# eLite_Clock_-_Display_Boards.net
KiCad netlist of a schematic drawn in EAGLE
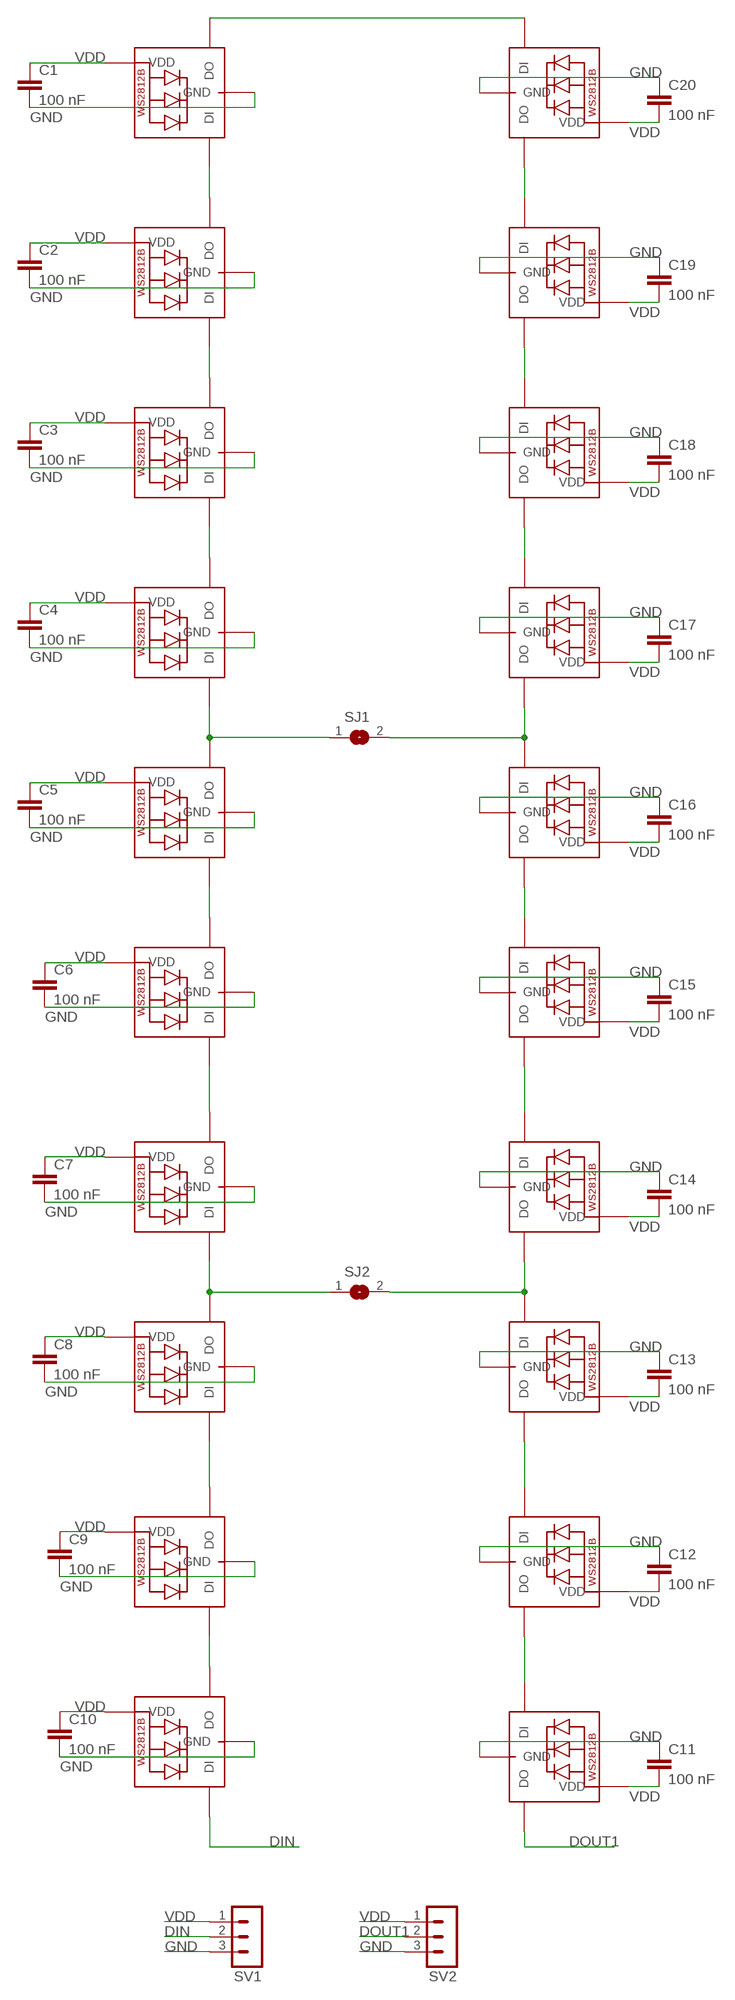
[diagram p0: schematic, sheet 1]

(export (version "E")
  (design (tool "Eeschema 10.0.6"))
  (components
    (comp (ref "C1")
      (value "100 nF")
      (footprint "eagle-import:C025-025X050")
      (libsource (lib "eagle-import") (part "C-EU025-025X050"))
    )
    (comp (ref "C2")
      (value "100 nF")
      (footprint "eagle-import:C025-025X050")
      (libsource (lib "eagle-import") (part "C-EU025-025X050"))
    )
    (comp (ref "C3")
      (value "100 nF")
      (footprint "eagle-import:C025-025X050")
      (libsource (lib "eagle-import") (part "C-EU025-025X050"))
    )
    (comp (ref "C4")
      (value "100 nF")
      (footprint "eagle-import:C025-025X050")
      (libsource (lib "eagle-import") (part "C-EU025-025X050"))
    )
    (comp (ref "C5")
      (value "100 nF")
      (footprint "eagle-import:C025-025X050")
      (libsource (lib "eagle-import") (part "C-EU025-025X050"))
    )
    (comp (ref "C6")
      (value "100 nF")
      (footprint "eagle-import:C025-025X050")
      (libsource (lib "eagle-import") (part "C-EU025-025X050"))
    )
    (comp (ref "C7")
      (value "100 nF")
      (footprint "eagle-import:C025-025X050")
      (libsource (lib "eagle-import") (part "C-EU025-025X050"))
    )
    (comp (ref "C8")
      (value "100 nF")
      (footprint "eagle-import:C025-025X050")
      (libsource (lib "eagle-import") (part "C-EU025-025X050"))
    )
    (comp (ref "C9")
      (value "100 nF")
      (footprint "eagle-import:C025-025X050")
      (libsource (lib "eagle-import") (part "C-EU025-025X050"))
    )
    (comp (ref "C10")
      (value "100 nF")
      (footprint "eagle-import:C025-025X050")
      (libsource (lib "eagle-import") (part "C-EU025-025X050"))
    )
    (comp (ref "C11")
      (value "100 nF")
      (footprint "eagle-import:C025-025X050")
      (libsource (lib "eagle-import") (part "C-EU025-025X050"))
    )
    (comp (ref "C12")
      (value "100 nF")
      (footprint "eagle-import:C025-025X050")
      (libsource (lib "eagle-import") (part "C-EU025-025X050"))
    )
    (comp (ref "C13")
      (value "100 nF")
      (footprint "eagle-import:C025-025X050")
      (libsource (lib "eagle-import") (part "C-EU025-025X050"))
    )
    (comp (ref "C14")
      (value "100 nF")
      (footprint "eagle-import:C025-025X050")
      (libsource (lib "eagle-import") (part "C-EU025-025X050"))
    )
    (comp (ref "C15")
      (value "100 nF")
      (footprint "eagle-import:C025-025X050")
      (libsource (lib "eagle-import") (part "C-EU025-025X050"))
    )
    (comp (ref "C16")
      (value "100 nF")
      (footprint "eagle-import:C025-025X050")
      (libsource (lib "eagle-import") (part "C-EU025-025X050"))
    )
    (comp (ref "C17")
      (value "100 nF")
      (footprint "eagle-import:C025-025X050")
      (libsource (lib "eagle-import") (part "C-EU025-025X050"))
    )
    (comp (ref "C18")
      (value "100 nF")
      (footprint "eagle-import:C025-025X050")
      (libsource (lib "eagle-import") (part "C-EU025-025X050"))
    )
    (comp (ref "C19")
      (value "100 nF")
      (footprint "eagle-import:C025-025X050")
      (libsource (lib "eagle-import") (part "C-EU025-025X050"))
    )
    (comp (ref "C20")
      (value "100 nF")
      (footprint "eagle-import:C025-025X050")
      (libsource (lib "eagle-import") (part "C-EU025-025X050"))
    )
    (comp (ref "LED1")
      (value "WS2812B_5050W")
      (footprint "eagle-import:WS2812B-WIDE")
      (libsource (lib "eagle-import") (part "WS2812B_5050W"))
    )
    (comp (ref "LED2")
      (value "WS2812B_5050W")
      (footprint "eagle-import:WS2812B-WIDE")
      (libsource (lib "eagle-import") (part "WS2812B_5050W"))
    )
    (comp (ref "LED3")
      (value "WS2812B_5050W")
      (footprint "eagle-import:WS2812B-WIDE")
      (libsource (lib "eagle-import") (part "WS2812B_5050W"))
    )
    (comp (ref "LED4")
      (value "WS2812B_5050W")
      (footprint "eagle-import:WS2812B-WIDE")
      (libsource (lib "eagle-import") (part "WS2812B_5050W"))
    )
    (comp (ref "LED5")
      (value "WS2812B_5050W")
      (footprint "eagle-import:WS2812B-WIDE")
      (libsource (lib "eagle-import") (part "WS2812B_5050W"))
    )
    (comp (ref "LED6")
      (value "WS2812B_5050W")
      (footprint "eagle-import:WS2812B-WIDE")
      (libsource (lib "eagle-import") (part "WS2812B_5050W"))
    )
    (comp (ref "LED7")
      (value "WS2812B_5050W")
      (footprint "eagle-import:WS2812B-WIDE")
      (libsource (lib "eagle-import") (part "WS2812B_5050W"))
    )
    (comp (ref "LED8")
      (value "WS2812B_5050W")
      (footprint "eagle-import:WS2812B-WIDE")
      (libsource (lib "eagle-import") (part "WS2812B_5050W"))
    )
    (comp (ref "LED9")
      (value "WS2812B_5050W")
      (footprint "eagle-import:WS2812B-WIDE")
      (libsource (lib "eagle-import") (part "WS2812B_5050W"))
    )
    (comp (ref "LED10")
      (value "WS2812B_5050W")
      (footprint "eagle-import:WS2812B-WIDE")
      (libsource (lib "eagle-import") (part "WS2812B_5050W"))
    )
    (comp (ref "LED11")
      (value "WS2812B_5050W")
      (footprint "eagle-import:WS2812B-WIDE")
      (libsource (lib "eagle-import") (part "WS2812B_5050W"))
    )
    (comp (ref "LED12")
      (value "WS2812B_5050W")
      (footprint "eagle-import:WS2812B-WIDE")
      (libsource (lib "eagle-import") (part "WS2812B_5050W"))
    )
    (comp (ref "LED13")
      (value "WS2812B_5050W")
      (footprint "eagle-import:WS2812B-WIDE")
      (libsource (lib "eagle-import") (part "WS2812B_5050W"))
    )
    (comp (ref "LED14")
      (value "WS2812B_5050W")
      (footprint "eagle-import:WS2812B-WIDE")
      (libsource (lib "eagle-import") (part "WS2812B_5050W"))
    )
    (comp (ref "LED15")
      (value "WS2812B_5050W")
      (footprint "eagle-import:WS2812B-WIDE")
      (libsource (lib "eagle-import") (part "WS2812B_5050W"))
    )
    (comp (ref "LED16")
      (value "WS2812B_5050W")
      (footprint "eagle-import:WS2812B-WIDE")
      (libsource (lib "eagle-import") (part "WS2812B_5050W"))
    )
    (comp (ref "LED17")
      (value "WS2812B_5050W")
      (footprint "eagle-import:WS2812B-WIDE")
      (libsource (lib "eagle-import") (part "WS2812B_5050W"))
    )
    (comp (ref "LED18")
      (value "WS2812B_5050W")
      (footprint "eagle-import:WS2812B-WIDE")
      (libsource (lib "eagle-import") (part "WS2812B_5050W"))
    )
    (comp (ref "LED19")
      (value "WS2812B_5050W")
      (footprint "eagle-import:WS2812B-WIDE")
      (libsource (lib "eagle-import") (part "WS2812B_5050W"))
    )
    (comp (ref "LED20")
      (value "WS2812B_5050W")
      (footprint "eagle-import:WS2812B-WIDE")
      (libsource (lib "eagle-import") (part "WS2812B_5050W"))
    )
    (comp (ref "SJ1") (value "SJ") (footprint "eagle-import:SJ") (libsource (lib "eagle-import") (part "SJ")))
    (comp (ref "SJ2") (value "SJ") (footprint "eagle-import:SJ") (libsource (lib "eagle-import") (part "SJ")))
    (comp (ref "SV1")
      (value "MA03-1")
      (footprint "eagle-import:MA03-1")
      (libsource (lib "eagle-import") (part "MA03-1"))
    )
    (comp (ref "SV2")
      (value "MA03-1")
      (footprint "eagle-import:MA03-1")
      (libsource (lib "eagle-import") (part "MA03-1"))
    )
  )
  (nets
    (net (code "1") (name "/DIN") (class "Default")
      (node (ref "LED1") (pin "4-DIN") (pinfunction "DI_4-DIN") (pintype "input"))
      (node (ref "SV1") (pin "2") (pinfunction "2_2") (pintype "passive"))
    )
    (net (code "2") (name "/DOUT1") (class "Default")
      (node (ref "LED20") (pin "2-DOUT") (pinfunction "DO_2-DOUT") (pintype "output"))
      (node (ref "SV2") (pin "2") (pinfunction "2_2") (pintype "passive"))
    )
    (net (code "3") (name "/GND") (class "Default")
      (node (ref "C1") (pin "2") (pinfunction "2_2") (pintype "passive"))
      (node (ref "C10") (pin "2") (pinfunction "2_2") (pintype "passive"))
      (node (ref "C11") (pin "1") (pinfunction "1_1") (pintype "passive"))
      (node (ref "C12") (pin "1") (pinfunction "1_1") (pintype "passive"))
      (node (ref "C13") (pin "1") (pinfunction "1_1") (pintype "passive"))
      (node (ref "C14") (pin "1") (pinfunction "1_1") (pintype "passive"))
      (node (ref "C15") (pin "1") (pinfunction "1_1") (pintype "passive"))
      (node (ref "C16") (pin "1") (pinfunction "1_1") (pintype "passive"))
      (node (ref "C17") (pin "1") (pinfunction "1_1") (pintype "passive"))
      (node (ref "C18") (pin "1") (pinfunction "1_1") (pintype "passive"))
      (node (ref "C19") (pin "1") (pinfunction "1_1") (pintype "passive"))
      (node (ref "C2") (pin "2") (pinfunction "2_2") (pintype "passive"))
      (node (ref "C20") (pin "1") (pinfunction "1_1") (pintype "passive"))
      (node (ref "C3") (pin "2") (pinfunction "2_2") (pintype "passive"))
      (node (ref "C4") (pin "2") (pinfunction "2_2") (pintype "passive"))
      (node (ref "C5") (pin "2") (pinfunction "2_2") (pintype "passive"))
      (node (ref "C6") (pin "2") (pinfunction "2_2") (pintype "passive"))
      (node (ref "C7") (pin "2") (pinfunction "2_2") (pintype "passive"))
      (node (ref "C8") (pin "2") (pinfunction "2_2") (pintype "passive"))
      (node (ref "C9") (pin "2") (pinfunction "2_2") (pintype "passive"))
      (node (ref "LED1") (pin "3-GND") (pinfunction "GND_3-GND") (pintype "power_in"))
      (node (ref "LED10") (pin "3-GND") (pinfunction "GND_3-GND") (pintype "power_in"))
      (node (ref "LED11") (pin "3-GND") (pinfunction "GND_3-GND") (pintype "power_in"))
      (node (ref "LED12") (pin "3-GND") (pinfunction "GND_3-GND") (pintype "power_in"))
      (node (ref "LED13") (pin "3-GND") (pinfunction "GND_3-GND") (pintype "power_in"))
      (node (ref "LED14") (pin "3-GND") (pinfunction "GND_3-GND") (pintype "power_in"))
      (node (ref "LED15") (pin "3-GND") (pinfunction "GND_3-GND") (pintype "power_in"))
      (node (ref "LED16") (pin "3-GND") (pinfunction "GND_3-GND") (pintype "power_in"))
      (node (ref "LED17") (pin "3-GND") (pinfunction "GND_3-GND") (pintype "power_in"))
      (node (ref "LED18") (pin "3-GND") (pinfunction "GND_3-GND") (pintype "power_in"))
      (node (ref "LED19") (pin "3-GND") (pinfunction "GND_3-GND") (pintype "power_in"))
      (node (ref "LED2") (pin "3-GND") (pinfunction "GND_3-GND") (pintype "power_in"))
      (node (ref "LED20") (pin "3-GND") (pinfunction "GND_3-GND") (pintype "power_in"))
      (node (ref "LED3") (pin "3-GND") (pinfunction "GND_3-GND") (pintype "power_in"))
      (node (ref "LED4") (pin "3-GND") (pinfunction "GND_3-GND") (pintype "power_in"))
      (node (ref "LED5") (pin "3-GND") (pinfunction "GND_3-GND") (pintype "power_in"))
      (node (ref "LED6") (pin "3-GND") (pinfunction "GND_3-GND") (pintype "power_in"))
      (node (ref "LED7") (pin "3-GND") (pinfunction "GND_3-GND") (pintype "power_in"))
      (node (ref "LED8") (pin "3-GND") (pinfunction "GND_3-GND") (pintype "power_in"))
      (node (ref "LED9") (pin "3-GND") (pinfunction "GND_3-GND") (pintype "power_in"))
      (node (ref "SV1") (pin "3") (pinfunction "3_3") (pintype "passive"))
      (node (ref "SV2") (pin "3") (pinfunction "3_3") (pintype "passive"))
    )
    (net (code "4") (name "/VDD") (class "Default")
      (node (ref "C1") (pin "1") (pinfunction "1_1") (pintype "passive"))
      (node (ref "C10") (pin "1") (pinfunction "1_1") (pintype "passive"))
      (node (ref "C11") (pin "2") (pinfunction "2_2") (pintype "passive"))
      (node (ref "C12") (pin "2") (pinfunction "2_2") (pintype "passive"))
      (node (ref "C13") (pin "2") (pinfunction "2_2") (pintype "passive"))
      (node (ref "C14") (pin "2") (pinfunction "2_2") (pintype "passive"))
      (node (ref "C15") (pin "2") (pinfunction "2_2") (pintype "passive"))
      (node (ref "C16") (pin "2") (pinfunction "2_2") (pintype "passive"))
      (node (ref "C17") (pin "2") (pinfunction "2_2") (pintype "passive"))
      (node (ref "C18") (pin "2") (pinfunction "2_2") (pintype "passive"))
      (node (ref "C19") (pin "2") (pinfunction "2_2") (pintype "passive"))
      (node (ref "C2") (pin "1") (pinfunction "1_1") (pintype "passive"))
      (node (ref "C20") (pin "2") (pinfunction "2_2") (pintype "passive"))
      (node (ref "C3") (pin "1") (pinfunction "1_1") (pintype "passive"))
      (node (ref "C4") (pin "1") (pinfunction "1_1") (pintype "passive"))
      (node (ref "C5") (pin "1") (pinfunction "1_1") (pintype "passive"))
      (node (ref "C6") (pin "1") (pinfunction "1_1") (pintype "passive"))
      (node (ref "C7") (pin "1") (pinfunction "1_1") (pintype "passive"))
      (node (ref "C8") (pin "1") (pinfunction "1_1") (pintype "passive"))
      (node (ref "C9") (pin "1") (pinfunction "1_1") (pintype "passive"))
      (node (ref "LED1") (pin "1-VDD") (pinfunction "VDD_1-VDD") (pintype "power_in"))
      (node (ref "LED10") (pin "1-VDD") (pinfunction "VDD_1-VDD") (pintype "power_in"))
      (node (ref "LED11") (pin "1-VDD") (pinfunction "VDD_1-VDD") (pintype "power_in"))
      (node (ref "LED12") (pin "1-VDD") (pinfunction "VDD_1-VDD") (pintype "power_in"))
      (node (ref "LED13") (pin "1-VDD") (pinfunction "VDD_1-VDD") (pintype "power_in"))
      (node (ref "LED14") (pin "1-VDD") (pinfunction "VDD_1-VDD") (pintype "power_in"))
      (node (ref "LED15") (pin "1-VDD") (pinfunction "VDD_1-VDD") (pintype "power_in"))
      (node (ref "LED16") (pin "1-VDD") (pinfunction "VDD_1-VDD") (pintype "power_in"))
      (node (ref "LED17") (pin "1-VDD") (pinfunction "VDD_1-VDD") (pintype "power_in"))
      (node (ref "LED18") (pin "1-VDD") (pinfunction "VDD_1-VDD") (pintype "power_in"))
      (node (ref "LED19") (pin "1-VDD") (pinfunction "VDD_1-VDD") (pintype "power_in"))
      (node (ref "LED2") (pin "1-VDD") (pinfunction "VDD_1-VDD") (pintype "power_in"))
      (node (ref "LED20") (pin "1-VDD") (pinfunction "VDD_1-VDD") (pintype "power_in"))
      (node (ref "LED3") (pin "1-VDD") (pinfunction "VDD_1-VDD") (pintype "power_in"))
      (node (ref "LED4") (pin "1-VDD") (pinfunction "VDD_1-VDD") (pintype "power_in"))
      (node (ref "LED5") (pin "1-VDD") (pinfunction "VDD_1-VDD") (pintype "power_in"))
      (node (ref "LED6") (pin "1-VDD") (pinfunction "VDD_1-VDD") (pintype "power_in"))
      (node (ref "LED7") (pin "1-VDD") (pinfunction "VDD_1-VDD") (pintype "power_in"))
      (node (ref "LED8") (pin "1-VDD") (pinfunction "VDD_1-VDD") (pintype "power_in"))
      (node (ref "LED9") (pin "1-VDD") (pinfunction "VDD_1-VDD") (pintype "power_in"))
      (node (ref "SV1") (pin "1") (pinfunction "1_1") (pintype "passive"))
      (node (ref "SV2") (pin "1") (pinfunction "1_1") (pintype "passive"))
    )
    (net (code "5") (name "Net-(LED1-DO)") (class "Default")
      (node (ref "LED1") (pin "2-DOUT") (pinfunction "DO_2-DOUT") (pintype "output"))
      (node (ref "LED2") (pin "4-DIN") (pinfunction "DI_4-DIN") (pintype "input"))
    )
    (net (code "6") (name "Net-(LED2-DO)") (class "Default")
      (node (ref "LED2") (pin "2-DOUT") (pinfunction "DO_2-DOUT") (pintype "output"))
      (node (ref "LED3") (pin "4-DIN") (pinfunction "DI_4-DIN") (pintype "input"))
    )
    (net (code "7") (name "Net-(LED3-DO)") (class "Default")
      (node (ref "LED3") (pin "2-DOUT") (pinfunction "DO_2-DOUT") (pintype "output"))
      (node (ref "LED4") (pin "4-DIN") (pinfunction "DI_4-DIN") (pintype "input"))
      (node (ref "SJ2") (pin "1") (pinfunction "1_1") (pintype "passive"))
    )
    (net (code "8") (name "Net-(LED4-DO)") (class "Default")
      (node (ref "LED4") (pin "2-DOUT") (pinfunction "DO_2-DOUT") (pintype "output"))
      (node (ref "LED5") (pin "4-DIN") (pinfunction "DI_4-DIN") (pintype "input"))
    )
    (net (code "9") (name "Net-(LED5-DO)") (class "Default")
      (node (ref "LED5") (pin "2-DOUT") (pinfunction "DO_2-DOUT") (pintype "output"))
      (node (ref "LED6") (pin "4-DIN") (pinfunction "DI_4-DIN") (pintype "input"))
    )
    (net (code "10") (name "Net-(LED6-DO)") (class "Default")
      (node (ref "LED6") (pin "2-DOUT") (pinfunction "DO_2-DOUT") (pintype "output"))
      (node (ref "LED7") (pin "4-DIN") (pinfunction "DI_4-DIN") (pintype "input"))
      (node (ref "SJ1") (pin "1") (pinfunction "1_1") (pintype "passive"))
    )
    (net (code "11") (name "Net-(LED7-DO)") (class "Default")
      (node (ref "LED7") (pin "2-DOUT") (pinfunction "DO_2-DOUT") (pintype "output"))
      (node (ref "LED8") (pin "4-DIN") (pinfunction "DI_4-DIN") (pintype "input"))
    )
    (net (code "12") (name "Net-(LED8-DO)") (class "Default")
      (node (ref "LED8") (pin "2-DOUT") (pinfunction "DO_2-DOUT") (pintype "output"))
      (node (ref "LED9") (pin "4-DIN") (pinfunction "DI_4-DIN") (pintype "input"))
    )
    (net (code "13") (name "Net-(LED10-DI)") (class "Default")
      (node (ref "LED10") (pin "4-DIN") (pinfunction "DI_4-DIN") (pintype "input"))
      (node (ref "LED9") (pin "2-DOUT") (pinfunction "DO_2-DOUT") (pintype "output"))
    )
    (net (code "14") (name "Net-(LED10-DO)") (class "Default")
      (node (ref "LED10") (pin "2-DOUT") (pinfunction "DO_2-DOUT") (pintype "output"))
      (node (ref "LED11") (pin "4-DIN") (pinfunction "DI_4-DIN") (pintype "input"))
    )
    (net (code "15") (name "Net-(LED11-DO)") (class "Default")
      (node (ref "LED11") (pin "2-DOUT") (pinfunction "DO_2-DOUT") (pintype "output"))
      (node (ref "LED12") (pin "4-DIN") (pinfunction "DI_4-DIN") (pintype "input"))
    )
    (net (code "16") (name "Net-(LED12-DO)") (class "Default")
      (node (ref "LED12") (pin "2-DOUT") (pinfunction "DO_2-DOUT") (pintype "output"))
      (node (ref "LED13") (pin "4-DIN") (pinfunction "DI_4-DIN") (pintype "input"))
    )
    (net (code "17") (name "Net-(LED13-DO)") (class "Default")
      (node (ref "LED13") (pin "2-DOUT") (pinfunction "DO_2-DOUT") (pintype "output"))
      (node (ref "LED14") (pin "4-DIN") (pinfunction "DI_4-DIN") (pintype "input"))
    )
    (net (code "18") (name "Net-(LED14-DO)") (class "Default")
      (node (ref "LED14") (pin "2-DOUT") (pinfunction "DO_2-DOUT") (pintype "output"))
      (node (ref "LED15") (pin "4-DIN") (pinfunction "DI_4-DIN") (pintype "input"))
      (node (ref "SJ1") (pin "2") (pinfunction "2_2") (pintype "passive"))
    )
    (net (code "19") (name "Net-(LED15-DO)") (class "Default")
      (node (ref "LED15") (pin "2-DOUT") (pinfunction "DO_2-DOUT") (pintype "output"))
      (node (ref "LED16") (pin "4-DIN") (pinfunction "DI_4-DIN") (pintype "input"))
    )
    (net (code "20") (name "Net-(LED16-DO)") (class "Default")
      (node (ref "LED16") (pin "2-DOUT") (pinfunction "DO_2-DOUT") (pintype "output"))
      (node (ref "LED17") (pin "4-DIN") (pinfunction "DI_4-DIN") (pintype "input"))
    )
    (net (code "21") (name "Net-(LED17-DO)") (class "Default")
      (node (ref "LED17") (pin "2-DOUT") (pinfunction "DO_2-DOUT") (pintype "output"))
      (node (ref "LED18") (pin "4-DIN") (pinfunction "DI_4-DIN") (pintype "input"))
      (node (ref "SJ2") (pin "2") (pinfunction "2_2") (pintype "passive"))
    )
    (net (code "22") (name "Net-(LED18-DO)") (class "Default")
      (node (ref "LED18") (pin "2-DOUT") (pinfunction "DO_2-DOUT") (pintype "output"))
      (node (ref "LED19") (pin "4-DIN") (pinfunction "DI_4-DIN") (pintype "input"))
    )
    (net (code "23") (name "Net-(LED19-DO)") (class "Default")
      (node (ref "LED19") (pin "2-DOUT") (pinfunction "DO_2-DOUT") (pintype "output"))
      (node (ref "LED20") (pin "4-DIN") (pinfunction "DI_4-DIN") (pintype "input"))
    )
  )
)
